# v_0_1.net
KiCad netlist of a schematic drawn in EAGLE
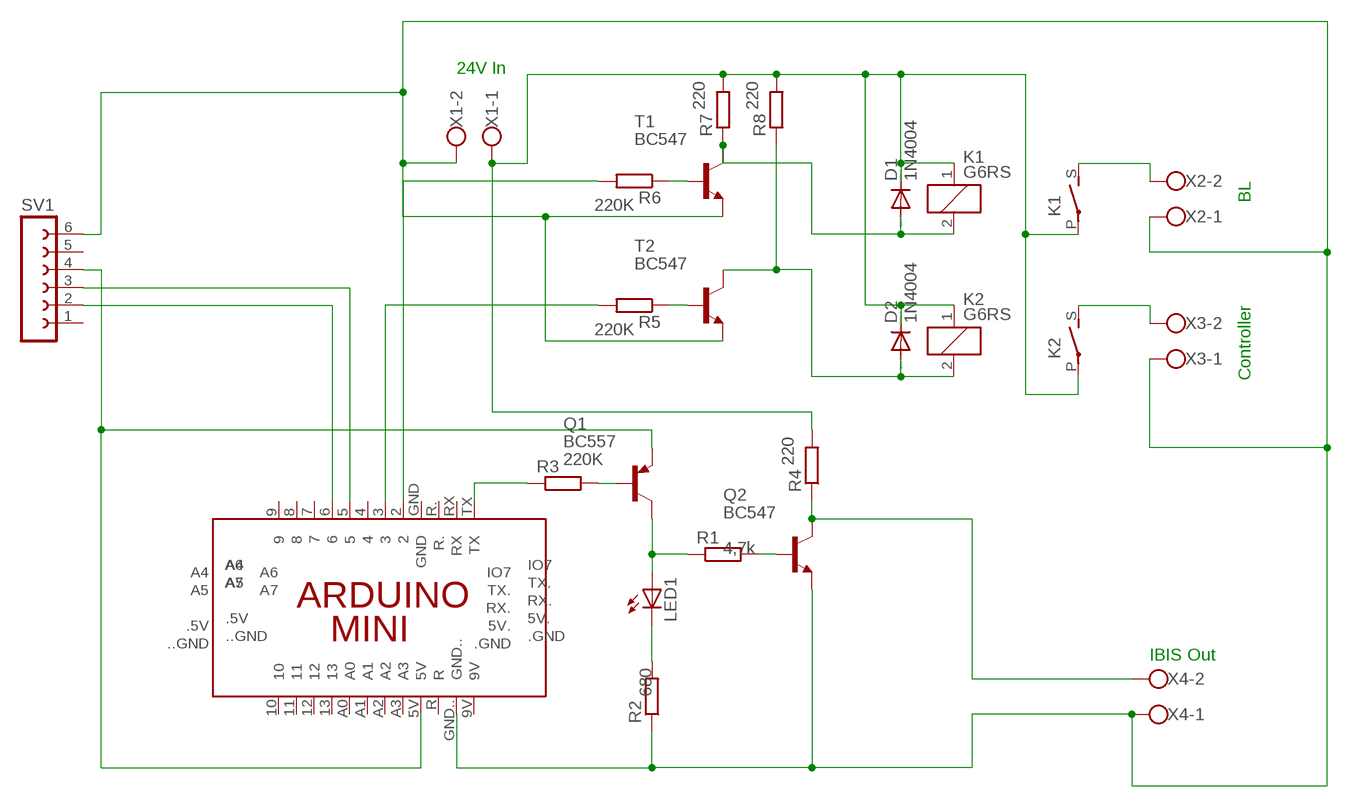
[diagram p0: schematic, sheet 1]

(export (version "E")
  (design (tool "Eeschema 10.0.6"))
  (components
    (comp (ref "D1")
      (value "1N4004")
      (footprint "eagle-import:DO41-10")
      (libsource (lib "eagle-import") (part "1N4004"))
    )
    (comp (ref "D2")
      (value "1N4004")
      (footprint "eagle-import:DO41-10")
      (libsource (lib "eagle-import") (part "1N4004"))
    )
    (comp (ref "K1")
      (value "G6RS")
      (footprint "eagle-import:G6RS")
      (libsource (lib "eagle-import") (part "G6RS"))
    )
    (comp (ref "K2")
      (value "G6RS")
      (footprint "eagle-import:G6RS")
      (libsource (lib "eagle-import") (part "G6RS"))
    )
    (comp (ref "LED1")
      (value "LED5MM")
      (footprint "eagle-import:LED5MM")
      (libsource (lib "eagle-import") (part "LED5MM"))
    )
    (comp (ref "PCB1")
      (value "ARDUINO_MINI")
      (footprint "eagle-import:ARDUINO_MINI")
      (libsource (lib "eagle-import") (part "ARDUINO_MINI"))
    )
    (comp (ref "Q1")
      (value "BC557")
      (footprint "eagle-import:TO92-EBC")
      (libsource (lib "eagle-import") (part "BC557"))
    )
    (comp (ref "Q2")
      (value "BC547")
      (footprint "eagle-import:TO92")
      (libsource (lib "eagle-import") (part "transistor-npn_BC547"))
    )
    (comp (ref "R1")
      (value "R-EU_0207/10")
      (footprint "eagle-import:0207_10")
      (fields (field (name "R") "4,7k"))
      (libsource (lib "eagle-import") (part "R-EU_0207/10"))
    )
    (comp (ref "R2")
      (value "R-EU_0207/10")
      (footprint "eagle-import:0207_10")
      (fields (field (name "R") "680"))
      (libsource (lib "eagle-import") (part "R-EU_0207/10"))
    )
    (comp (ref "R3")
      (value "R-EU_0207/10")
      (footprint "eagle-import:0207_10")
      (fields (field (name "R") "220K"))
      (libsource (lib "eagle-import") (part "R-EU_0207/10"))
    )
    (comp (ref "R4")
      (value "R-EU_0207/10")
      (footprint "eagle-import:0207_10")
      (fields (field (name "R") "220"))
      (libsource (lib "eagle-import") (part "R-EU_0207/10"))
    )
    (comp (ref "R5")
      (value "R-EU_0207/10")
      (footprint "eagle-import:0207_10")
      (fields (field (name "R") "220K"))
      (libsource (lib "eagle-import") (part "R-EU_0207/10"))
    )
    (comp (ref "R6")
      (value "R-EU_0207/10")
      (footprint "eagle-import:0207_10")
      (fields (field (name "R") "220K"))
      (libsource (lib "eagle-import") (part "R-EU_0207/10"))
    )
    (comp (ref "R7")
      (value "R-EU_0207/10")
      (footprint "eagle-import:0207_10")
      (fields (field (name "R") "220"))
      (libsource (lib "eagle-import") (part "R-EU_0207/10"))
    )
    (comp (ref "R8")
      (value "R-EU_0207/10")
      (footprint "eagle-import:0207_10")
      (fields (field (name "R") "220"))
      (libsource (lib "eagle-import") (part "R-EU_0207/10"))
    )
    (comp (ref "SV1")
      (value "FE06-1")
      (footprint "eagle-import:FE06")
      (libsource (lib "eagle-import") (part "FE06-1"))
    )
    (comp (ref "T1")
      (value "BC547")
      (footprint "eagle-import:TO92")
      (libsource (lib "eagle-import") (part "BC547"))
    )
    (comp (ref "T2")
      (value "BC547")
      (footprint "eagle-import:TO92")
      (libsource (lib "eagle-import") (part "BC547"))
    )
    (comp (ref "X1")
      (value "W237-102")
      (footprint "eagle-import:W237-102")
      (fields (field (name "MPN") "237-102"))
      (libsource (lib "eagle-import") (part "W237-102"))
    )
    (comp (ref "X2")
      (value "W237-102")
      (footprint "eagle-import:W237-102")
      (fields (field (name "MPN") "237-102"))
      (libsource (lib "eagle-import") (part "W237-102"))
    )
    (comp (ref "X3")
      (value "W237-102")
      (footprint "eagle-import:W237-102")
      (fields (field (name "MPN") "237-102"))
      (libsource (lib "eagle-import") (part "W237-102"))
    )
    (comp (ref "X4")
      (value "W237-102")
      (footprint "eagle-import:W237-102")
      (fields (field (name "MPN") "237-102"))
      (libsource (lib "eagle-import") (part "W237-102"))
    )
  )
  (nets
    (net (code "1") (name "Net-(LED1-C)") (class "Default")
      (node (ref "LED1") (pin "K") (pinfunction "C_K") (pintype "passive"))
      (node (ref "R2") (pin "2") (pinfunction "2_2") (pintype "passive"))
    )
    (net (code "2") (name "Net-(LED1-PadA)") (class "Default")
      (node (ref "LED1") (pin "A") (pinfunction "A_A") (pintype "passive"))
      (node (ref "Q1") (pin "C") (pinfunction "C_C") (pintype "passive"))
      (node (ref "R1") (pin "1") (pinfunction "1_1") (pintype "passive"))
    )
    (net (code "3") (name "Net-(PCB1-Pad2)") (class "Default")
      (node (ref "PCB1") (pin "2") (pinfunction "2_2") (pintype "bidirectional"))
      (node (ref "R6") (pin "2") (pinfunction "2_2") (pintype "passive"))
    )
    (net (code "4") (name "Net-(PCB1-Pad3)") (class "Default")
      (node (ref "PCB1") (pin "3") (pinfunction "3_3") (pintype "bidirectional"))
      (node (ref "R5") (pin "2") (pinfunction "2_2") (pintype "passive"))
    )
    (net (code "5") (name "Net-(PCB1-Pad5)") (class "Default")
      (node (ref "PCB1") (pin "5") (pinfunction "5_5") (pintype "bidirectional"))
      (node (ref "SV1") (pin "3") (pinfunction "3_3") (pintype "passive"))
    )
    (net (code "6") (name "Net-(PCB1-Pad5V)") (class "Default")
      (node (ref "PCB1") (pin "5V") (pinfunction "5V_5V") (pintype "bidirectional"))
      (node (ref "Q1") (pin "E") (pinfunction "E_E") (pintype "passive"))
      (node (ref "SV1") (pin "4") (pinfunction "4_4") (pintype "passive"))
    )
    (net (code "7") (name "Net-(PCB1-Pad6)") (class "Default")
      (node (ref "PCB1") (pin "6") (pinfunction "6_6") (pintype "bidirectional"))
      (node (ref "SV1") (pin "2") (pinfunction "2_2") (pintype "passive"))
    )
    (net (code "8") (name "Net-(PCB1-PadTX)") (class "Default")
      (node (ref "PCB1") (pin "TX") (pinfunction "TX_TX") (pintype "bidirectional"))
      (node (ref "R3") (pin "1") (pinfunction "1_1") (pintype "passive"))
    )
    (net (code "9") (name "Net-(Q1-PadB)") (class "Default")
      (node (ref "Q1") (pin "B") (pinfunction "B_B") (pintype "passive"))
      (node (ref "R3") (pin "2") (pinfunction "2_2") (pintype "passive"))
    )
    (net (code "10") (name "Net-(Q2-B)") (class "Default")
      (node (ref "Q2") (pin "2") (pinfunction "B_2") (pintype "passive"))
      (node (ref "R1") (pin "2") (pinfunction "2_2") (pintype "passive"))
    )
    (net (code "11") (name "Net-(Q2-C)") (class "Default")
      (node (ref "Q2") (pin "3") (pinfunction "C_3") (pintype "passive"))
      (node (ref "R4") (pin "1") (pinfunction "1_1") (pintype "passive"))
      (node (ref "X4") (pin "2") (pinfunction "KL_2") (pintype "passive"))
    )
    (net (code "12") (name "Net-(Q2-E)") (class "Default")
      (node (ref "PCB1") (pin "GND..") (pinfunction "GND.._GND..") (pintype "bidirectional"))
      (node (ref "Q2") (pin "1") (pinfunction "E_1") (pintype "passive"))
      (node (ref "R2") (pin "1") (pinfunction "1_1") (pintype "passive"))
      (node (ref "SV1") (pin "6") (pinfunction "6_6") (pintype "passive"))
      (node (ref "T1") (pin "1") (pinfunction "E_1") (pintype "passive"))
      (node (ref "T2") (pin "1") (pinfunction "E_1") (pintype "passive"))
      (node (ref "X1") (pin "2") (pinfunction "KL_2") (pintype "passive"))
      (node (ref "X2") (pin "1") (pinfunction "KL_1") (pintype "passive"))
      (node (ref "X3") (pin "1") (pinfunction "KL_1") (pintype "passive"))
      (node (ref "X4") (pin "1") (pinfunction "KL_1") (pintype "passive"))
    )
    (net (code "13") (name "Net-(T1-B)") (class "Default")
      (node (ref "R6") (pin "1") (pinfunction "1_1") (pintype "passive"))
      (node (ref "T1") (pin "2") (pinfunction "B_2") (pintype "passive"))
    )
    (net (code "14") (name "Net-(T1-C)") (class "Default")
      (node (ref "D1") (pin "A") (pinfunction "A_A") (pintype "passive"))
      (node (ref "K1") (pin "2") (pinfunction "2_2") (pintype "passive"))
      (node (ref "R7") (pin "1") (pinfunction "1_1") (pintype "passive"))
      (node (ref "T1") (pin "3") (pinfunction "C_3") (pintype "passive"))
    )
    (net (code "15") (name "Net-(T2-B)") (class "Default")
      (node (ref "R5") (pin "1") (pinfunction "1_1") (pintype "passive"))
      (node (ref "T2") (pin "2") (pinfunction "B_2") (pintype "passive"))
    )
    (net (code "16") (name "Net-(T2-C)") (class "Default")
      (node (ref "D2") (pin "A") (pinfunction "A_A") (pintype "passive"))
      (node (ref "K2") (pin "2") (pinfunction "2_2") (pintype "passive"))
      (node (ref "R8") (pin "1") (pinfunction "1_1") (pintype "passive"))
      (node (ref "T2") (pin "3") (pinfunction "C_3") (pintype "passive"))
    )
    (net (code "17") (name "Net-(X1A-KL)") (class "Default")
      (node (ref "D1") (pin "C") (pinfunction "C_C") (pintype "passive"))
      (node (ref "D2") (pin "C") (pinfunction "C_C") (pintype "passive"))
      (node (ref "K1") (pin "1") (pinfunction "1_1") (pintype "passive"))
      (node (ref "K1") (pin "P") (pinfunction "P_P") (pintype "passive"))
      (node (ref "K2") (pin "1") (pinfunction "1_1") (pintype "passive"))
      (node (ref "K2") (pin "P") (pinfunction "P_P") (pintype "passive"))
      (node (ref "R4") (pin "2") (pinfunction "2_2") (pintype "passive"))
      (node (ref "R7") (pin "2") (pinfunction "2_2") (pintype "passive"))
      (node (ref "R8") (pin "2") (pinfunction "2_2") (pintype "passive"))
      (node (ref "X1") (pin "1") (pinfunction "KL_1") (pintype "passive"))
    )
    (net (code "18") (name "Net-(X2B-KL)") (class "Default")
      (node (ref "K1") (pin "S") (pinfunction "S_S") (pintype "passive"))
      (node (ref "X2") (pin "2") (pinfunction "KL_2") (pintype "passive"))
    )
    (net (code "19") (name "Net-(X3B-KL)") (class "Default")
      (node (ref "K2") (pin "S") (pinfunction "S_S") (pintype "passive"))
      (node (ref "X3") (pin "2") (pinfunction "KL_2") (pintype "passive"))
    )
    (net (code "20") (name "unconnected-(PCB1-Pad..GND)") (class "Default")
      (node (ref "PCB1") (pin "..GND") (pinfunction "..GND_..GND") (pintype "bidirectional"))
    )
    (net (code "21") (name "unconnected-(PCB1-Pad.5V)") (class "Default")
      (node (ref "PCB1") (pin ".5V") (pinfunction ".5V_.5V") (pintype "bidirectional"))
    )
    (net (code "22") (name "unconnected-(PCB1-Pad.GND)") (class "Default")
      (node (ref "PCB1") (pin ".GND") (pinfunction ".GND_.GND") (pintype "bidirectional"))
    )
    (net (code "23") (name "unconnected-(PCB1-Pad4)") (class "Default")
      (node (ref "PCB1") (pin "4") (pinfunction "4_4") (pintype "bidirectional"))
    )
    (net (code "24") (name "unconnected-(PCB1-Pad5V.)") (class "Default")
      (node (ref "PCB1") (pin "5V.") (pinfunction "5V._5V.") (pintype "bidirectional"))
    )
    (net (code "25") (name "unconnected-(PCB1-Pad7)") (class "Default")
      (node (ref "PCB1") (pin "7") (pinfunction "7_7") (pintype "bidirectional"))
    )
    (net (code "26") (name "unconnected-(PCB1-Pad8)") (class "Default")
      (node (ref "PCB1") (pin "8") (pinfunction "8_8") (pintype "bidirectional"))
    )
    (net (code "27") (name "unconnected-(PCB1-Pad9)") (class "Default")
      (node (ref "PCB1") (pin "9") (pinfunction "9_9") (pintype "bidirectional"))
    )
    (net (code "28") (name "unconnected-(PCB1-Pad9V)") (class "Default")
      (node (ref "PCB1") (pin "9V") (pinfunction "9V_9V") (pintype "bidirectional"))
    )
    (net (code "29") (name "unconnected-(PCB1-Pad10)") (class "Default")
      (node (ref "PCB1") (pin "10") (pinfunction "10_10") (pintype "bidirectional"))
    )
    (net (code "30") (name "unconnected-(PCB1-Pad11)") (class "Default")
      (node (ref "PCB1") (pin "11") (pinfunction "11_11") (pintype "bidirectional"))
    )
    (net (code "31") (name "unconnected-(PCB1-Pad12)") (class "Default")
      (node (ref "PCB1") (pin "12") (pinfunction "12_12") (pintype "bidirectional"))
    )
    (net (code "32") (name "unconnected-(PCB1-Pad13)") (class "Default")
      (node (ref "PCB1") (pin "13") (pinfunction "13_13") (pintype "bidirectional"))
    )
    (net (code "33") (name "unconnected-(PCB1-PadA0)") (class "Default")
      (node (ref "PCB1") (pin "A0") (pinfunction "A0_A0") (pintype "bidirectional"))
    )
    (net (code "34") (name "unconnected-(PCB1-PadA1)") (class "Default")
      (node (ref "PCB1") (pin "A1") (pinfunction "A1_A1") (pintype "bidirectional"))
    )
    (net (code "35") (name "unconnected-(PCB1-PadA2)") (class "Default")
      (node (ref "PCB1") (pin "A2") (pinfunction "A2_A2") (pintype "bidirectional"))
    )
    (net (code "36") (name "unconnected-(PCB1-PadA3)") (class "Default")
      (node (ref "PCB1") (pin "A3") (pinfunction "A3_A3") (pintype "bidirectional"))
    )
    (net (code "37") (name "unconnected-(PCB1-PadA4)") (class "Default")
      (node (ref "PCB1") (pin "A4") (pinfunction "A4_A4") (pintype "bidirectional"))
    )
    (net (code "38") (name "unconnected-(PCB1-PadA5)") (class "Default")
      (node (ref "PCB1") (pin "A5") (pinfunction "A5_A5") (pintype "bidirectional"))
    )
    (net (code "39") (name "unconnected-(PCB1-PadA6)") (class "Default")
      (node (ref "PCB1") (pin "A6") (pinfunction "A6_A6") (pintype "bidirectional"))
    )
    (net (code "40") (name "unconnected-(PCB1-PadA7)") (class "Default")
      (node (ref "PCB1") (pin "A7") (pinfunction "A7_A7") (pintype "bidirectional"))
    )
    (net (code "41") (name "unconnected-(PCB1-PadGND)") (class "Default")
      (node (ref "PCB1") (pin "GND") (pinfunction "GND_GND") (pintype "bidirectional"))
    )
    (net (code "42") (name "unconnected-(PCB1-PadIO7)") (class "Default")
      (node (ref "PCB1") (pin "IO7") (pinfunction "IO7_IO7") (pintype "bidirectional"))
    )
    (net (code "43") (name "unconnected-(PCB1-PadR)") (class "Default")
      (node (ref "PCB1") (pin "R") (pinfunction "R_R") (pintype "bidirectional"))
    )
    (net (code "44") (name "unconnected-(PCB1-PadR.)") (class "Default")
      (node (ref "PCB1") (pin "R.") (pinfunction "R._R.") (pintype "bidirectional"))
    )
    (net (code "45") (name "unconnected-(PCB1-PadRX)") (class "Default")
      (node (ref "PCB1") (pin "RX") (pinfunction "RX_RX") (pintype "bidirectional"))
    )
    (net (code "46") (name "unconnected-(PCB1-PadRX.)") (class "Default")
      (node (ref "PCB1") (pin "RX.") (pinfunction "RX._RX.") (pintype "bidirectional"))
    )
    (net (code "47") (name "unconnected-(PCB1-PadTX.)") (class "Default")
      (node (ref "PCB1") (pin "TX.") (pinfunction "TX._TX.") (pintype "bidirectional"))
    )
    (net (code "48") (name "unconnected-(SV1-Pad1)") (class "Default")
      (node (ref "SV1") (pin "1") (pinfunction "1_1") (pintype "passive"))
    )
    (net (code "49") (name "unconnected-(SV1-Pad5)") (class "Default")
      (node (ref "SV1") (pin "5") (pinfunction "5_5") (pintype "passive"))
    )
  )
)
